# TSOC_Block_Template_Dual_PTH.net
KiCad netlist of a schematic drawn in EAGLE
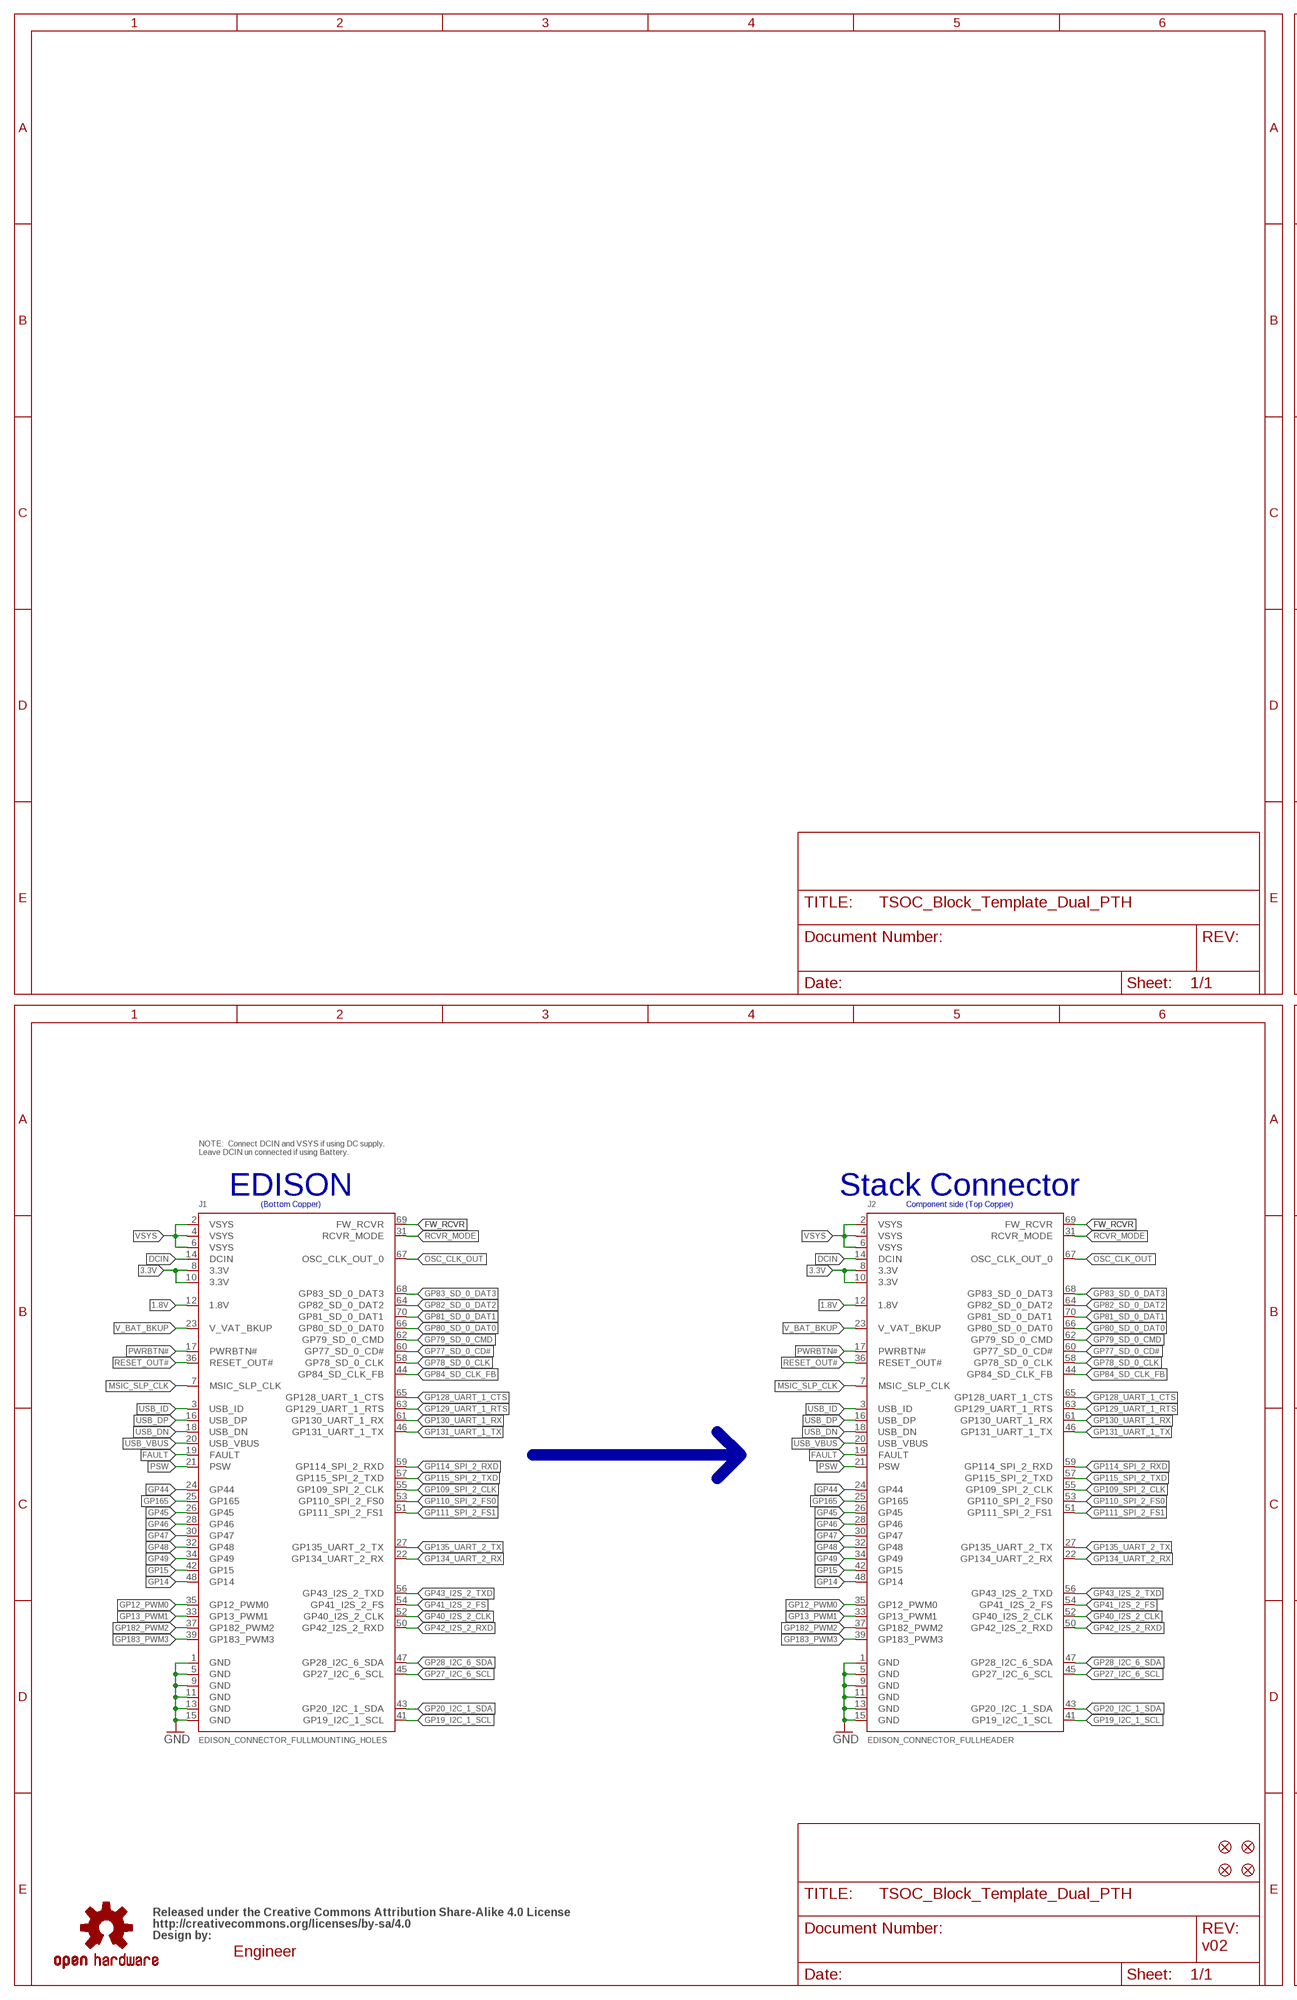
[diagram p0: schematic, sheet 1, part 1 of 2]
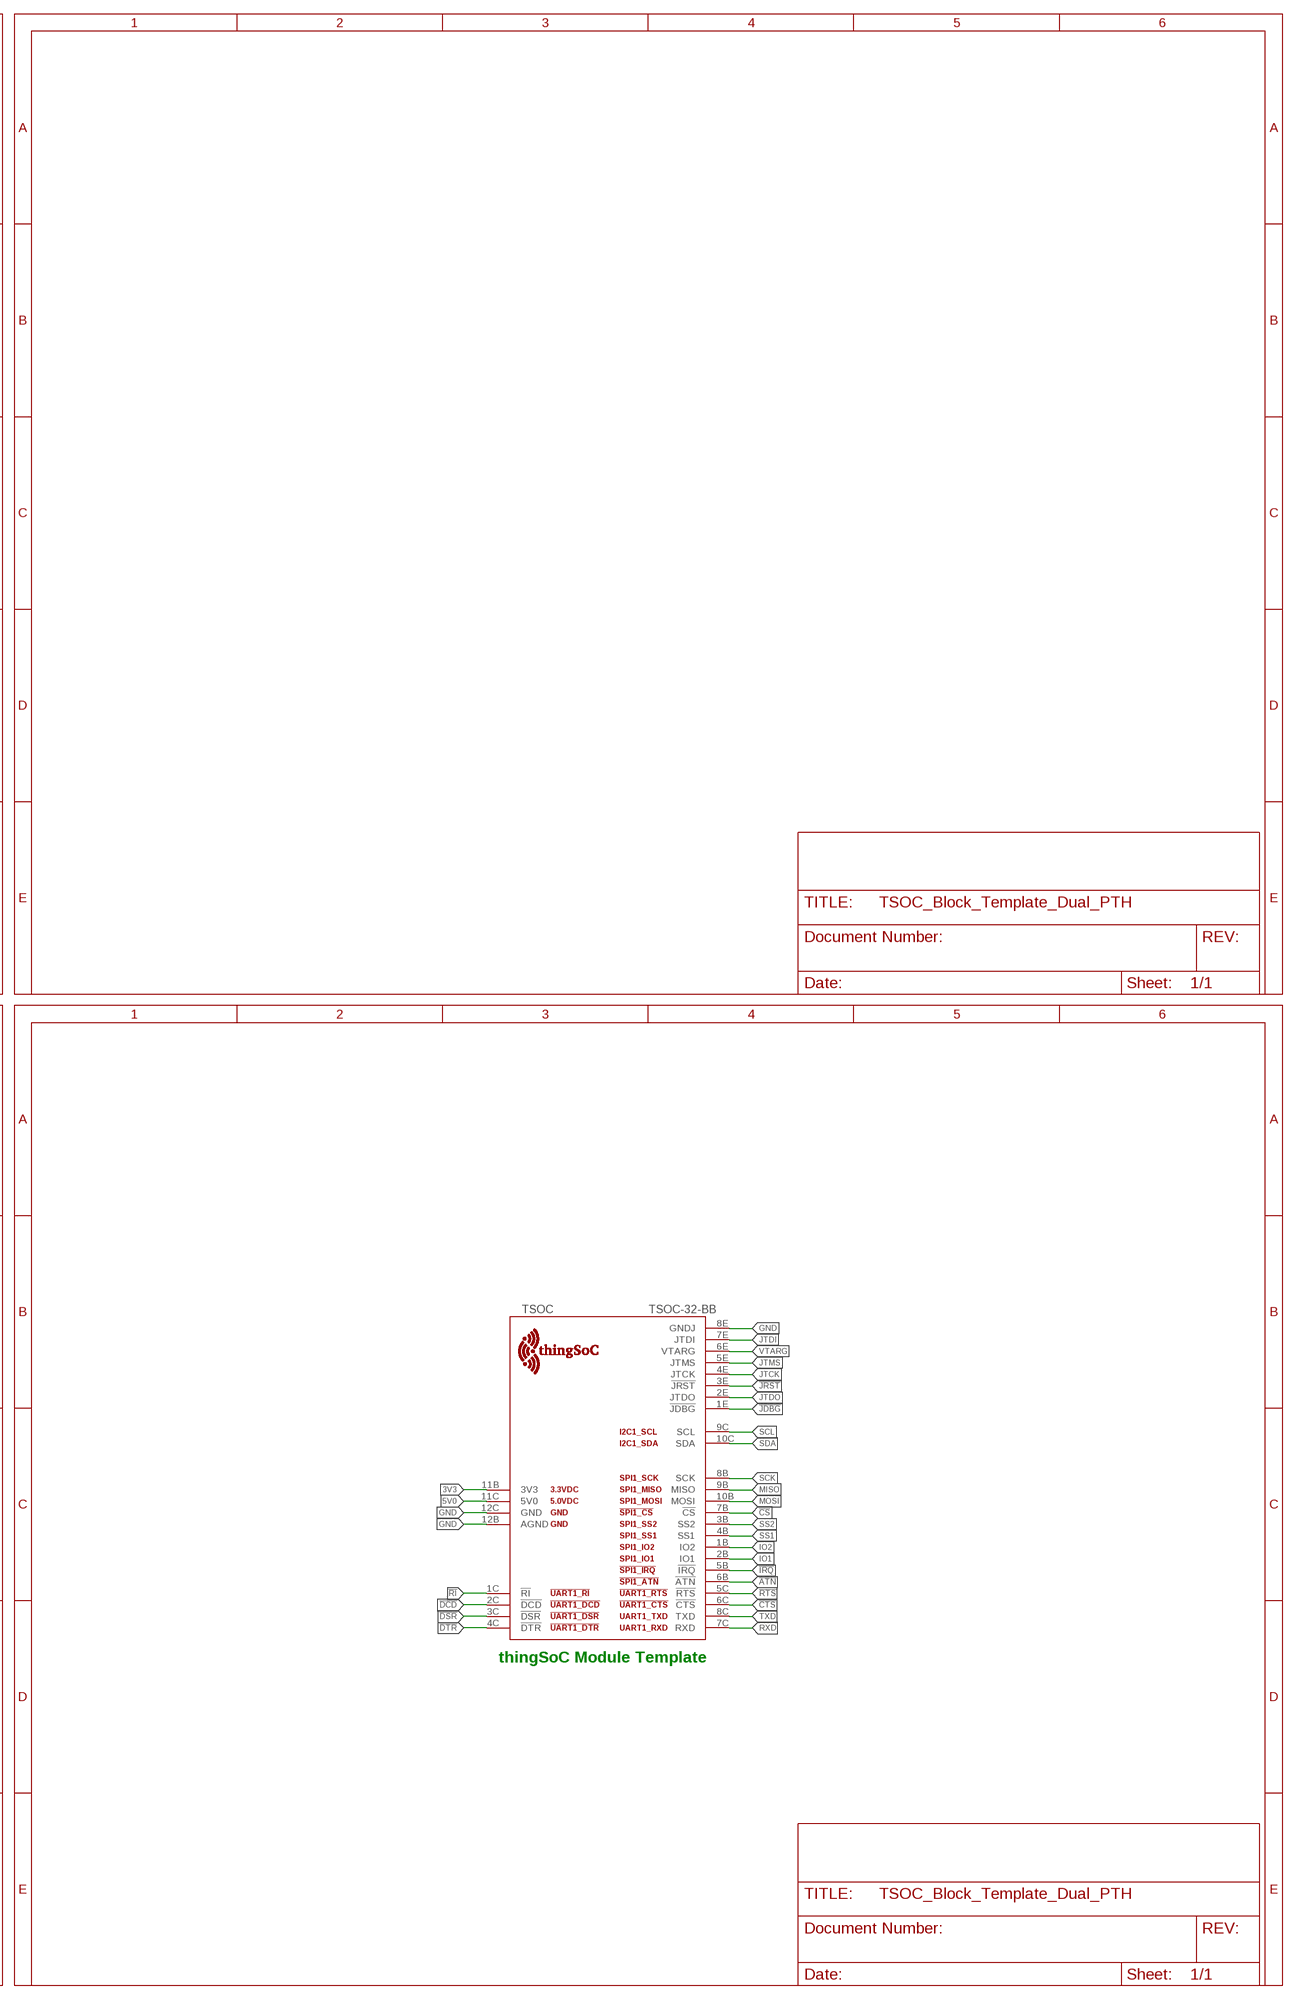
[diagram p1: schematic, sheet 1, part 2 of 2]

(export (version "E")
  (design (tool "Eeschema 10.0.6"))
  (components
    (comp (ref "FID5")
      (value "FIDUCIAL1X2")
      (footprint "eagle-import:FIDUCIAL-1X2")
      (libsource (lib "eagle-import") (part "FIDUCIAL1X2"))
    )
    (comp (ref "FID6")
      (value "FIDUCIAL1X2")
      (footprint "eagle-import:FIDUCIAL-1X2")
      (libsource (lib "eagle-import") (part "FIDUCIAL1X2"))
    )
    (comp (ref "FID7")
      (value "FIDUCIAL1X2")
      (footprint "eagle-import:FIDUCIAL-1X2")
      (libsource (lib "eagle-import") (part "FIDUCIAL1X2"))
    )
    (comp (ref "FID8")
      (value "FIDUCIAL1X2")
      (footprint "eagle-import:FIDUCIAL-1X2")
      (libsource (lib "eagle-import") (part "FIDUCIAL1X2"))
    )
    (comp (ref "J1")
      (value "EDISON_CONNECTOR_FULLMOUNTING_HOLES")
      (footprint "eagle-import:EDISON_DAUGHTER")
      (libsource (lib "eagle-import") (part "EDISON_CONNECTOR_FULLMOUNTING_HOLES"))
    )
    (comp (ref "J2")
      (value "EDISON_CONNECTOR_FULLHEADER")
      (footprint "eagle-import:DF40C-70DP-0.4(51)")
      (libsource (lib "eagle-import") (part "EDISON_CONNECTOR_FULLHEADER"))
    )
    (comp (ref "LOGO5")
      (value "OSHW-LOGOS")
      (footprint "eagle-import:OSHW-LOGO-S")
      (libsource (lib "eagle-import") (part "OSHW-LOGOS"))
    )
    (comp (ref "TSOC")
      (value "TSOC-32-BB")
      (footprint "eagle-import:TSOC-BB-S32")
      (libsource (lib "eagle-import") (part "TSOC-32-BB"))
    )
    (comp (ref "U$1")
      (value "BY_CC_SA_TEXTTEXT")
      (footprint "eagle-import:BY_CC_SA_TEXT")
      (libsource (lib "eagle-import") (part "BY_CC_SA_TEXTTEXT"))
    )
  )
  (nets
    (net (code "1") (name "/~{ATN}") (class "Default")
      (node (ref "TSOC") (pin "6B") (pinfunction "~{ATN}_6B") (pintype "bidirectional"))
    )
    (net (code "2") (name "/~{CS}") (class "Default")
      (node (ref "TSOC") (pin "7B") (pinfunction "~{CS}_7B") (pintype "bidirectional"))
    )
    (net (code "3") (name "/~{CTS}") (class "Default")
      (node (ref "TSOC") (pin "6C") (pinfunction "~{CTS}_6C") (pintype "bidirectional"))
    )
    (net (code "4") (name "/~{DCD}") (class "Default")
      (node (ref "TSOC") (pin "2C") (pinfunction "~{DCD}_2C") (pintype "bidirectional"))
    )
    (net (code "5") (name "/~{DSR}") (class "Default")
      (node (ref "TSOC") (pin "3C") (pinfunction "~{DSR}_3C") (pintype "bidirectional"))
    )
    (net (code "6") (name "/~{DTR}") (class "Default")
      (node (ref "TSOC") (pin "4C") (pinfunction "~{DTR}_4C") (pintype "bidirectional"))
    )
    (net (code "7") (name "/~{IRQ}") (class "Default")
      (node (ref "TSOC") (pin "5B") (pinfunction "~{IRQ}_5B") (pintype "bidirectional"))
    )
    (net (code "8") (name "/~{JDBG}") (class "Default")
      (node (ref "TSOC") (pin "1E") (pinfunction "~{JDBG}_1E") (pintype "bidirectional"))
    )
    (net (code "9") (name "/~{JRST}") (class "Default")
      (node (ref "TSOC") (pin "3E") (pinfunction "~{JRST}_3E") (pintype "bidirectional"))
    )
    (net (code "10") (name "/~{RI}") (class "Default")
      (node (ref "TSOC") (pin "1C") (pinfunction "~{RI}_1C") (pintype "bidirectional"))
    )
    (net (code "11") (name "/~{RTS}") (class "Default")
      (node (ref "TSOC") (pin "5C") (pinfunction "~{RTS}_5C") (pintype "bidirectional"))
    )
    (net (code "12") (name "1.8V") (class "Default")
      (node (ref "J1") (pin "12") (pinfunction "1.8V_12") (pintype "bidirectional"))
      (node (ref "J2") (pin "12") (pinfunction "1.8V_12") (pintype "bidirectional"))
    )
    (net (code "13") (name "3.3V") (class "Default")
      (node (ref "J1") (pin "10") (pinfunction "3.3V_10") (pintype "bidirectional"))
      (node (ref "J1") (pin "8") (pinfunction "3.3V_8") (pintype "bidirectional"))
      (node (ref "J2") (pin "10") (pinfunction "3.3V_10") (pintype "bidirectional"))
      (node (ref "J2") (pin "8") (pinfunction "3.3V_8") (pintype "bidirectional"))
    )
    (net (code "14") (name "3V3") (class "Default")
      (node (ref "TSOC") (pin "11B") (pinfunction "3V3_11B") (pintype "bidirectional"))
    )
    (net (code "15") (name "5V0") (class "Default")
      (node (ref "TSOC") (pin "11C") (pinfunction "5V0_11C") (pintype "bidirectional"))
    )
    (net (code "16") (name "DCIN") (class "Default")
      (node (ref "J1") (pin "14") (pinfunction "DCIN_14") (pintype "bidirectional"))
      (node (ref "J2") (pin "14") (pinfunction "DCIN_14") (pintype "bidirectional"))
    )
    (net (code "17") (name "FAULT") (class "Default")
      (node (ref "J1") (pin "19") (pinfunction "FAULT_19") (pintype "bidirectional"))
      (node (ref "J2") (pin "19") (pinfunction "FAULT_19") (pintype "bidirectional"))
    )
    (net (code "18") (name "FW_RCVR") (class "Default")
      (node (ref "J1") (pin "69") (pinfunction "FW_RCVR_69") (pintype "bidirectional"))
      (node (ref "J2") (pin "69") (pinfunction "FW_RCVR_69") (pintype "bidirectional"))
    )
    (net (code "19") (name "GND") (class "Default")
      (node (ref "J1") (pin "1") (pinfunction "GND_1") (pintype "bidirectional"))
      (node (ref "J1") (pin "11") (pinfunction "GND_11") (pintype "bidirectional"))
      (node (ref "J1") (pin "13") (pinfunction "GND_13") (pintype "bidirectional"))
      (node (ref "J1") (pin "15") (pinfunction "GND_15") (pintype "bidirectional"))
      (node (ref "J1") (pin "5") (pinfunction "GND_5") (pintype "bidirectional"))
      (node (ref "J1") (pin "9") (pinfunction "GND_9") (pintype "bidirectional"))
      (node (ref "J2") (pin "1") (pinfunction "GND_1") (pintype "bidirectional"))
      (node (ref "J2") (pin "11") (pinfunction "GND_11") (pintype "bidirectional"))
      (node (ref "J2") (pin "13") (pinfunction "GND_13") (pintype "bidirectional"))
      (node (ref "J2") (pin "15") (pinfunction "GND_15") (pintype "bidirectional"))
      (node (ref "J2") (pin "5") (pinfunction "GND_5") (pintype "bidirectional"))
      (node (ref "J2") (pin "9") (pinfunction "GND_9") (pintype "bidirectional"))
      (node (ref "TSOC") (pin "12B") (pinfunction "AGND_12B") (pintype "bidirectional"))
      (node (ref "TSOC") (pin "12C") (pinfunction "GND_12C") (pintype "bidirectional"))
      (node (ref "TSOC") (pin "8E") (pinfunction "GNDJ_8E") (pintype "bidirectional"))
    )
    (net (code "20") (name "GP12_PWM0") (class "Default")
      (node (ref "J1") (pin "35") (pinfunction "GP12_PWM0_35") (pintype "bidirectional"))
      (node (ref "J2") (pin "35") (pinfunction "GP12_PWM0_35") (pintype "bidirectional"))
    )
    (net (code "21") (name "GP13_PWM1") (class "Default")
      (node (ref "J1") (pin "33") (pinfunction "GP13_PWM1_33") (pintype "bidirectional"))
      (node (ref "J2") (pin "33") (pinfunction "GP13_PWM1_33") (pintype "bidirectional"))
    )
    (net (code "22") (name "GP14") (class "Default")
      (node (ref "J1") (pin "48") (pinfunction "GP14_48") (pintype "bidirectional"))
      (node (ref "J2") (pin "48") (pinfunction "GP14_48") (pintype "bidirectional"))
    )
    (net (code "23") (name "GP15") (class "Default")
      (node (ref "J1") (pin "42") (pinfunction "GP15_42") (pintype "bidirectional"))
      (node (ref "J2") (pin "42") (pinfunction "GP15_42") (pintype "bidirectional"))
    )
    (net (code "24") (name "GP19_I2C_1_SCL") (class "Default")
      (node (ref "J1") (pin "41") (pinfunction "GP19_I2C_1_SCL_41") (pintype "bidirectional"))
      (node (ref "J2") (pin "41") (pinfunction "GP19_I2C_1_SCL_41") (pintype "bidirectional"))
    )
    (net (code "25") (name "GP20_I2C_1_SDA") (class "Default")
      (node (ref "J1") (pin "43") (pinfunction "GP20_I2C_1_SDA_43") (pintype "bidirectional"))
      (node (ref "J2") (pin "43") (pinfunction "GP20_I2C_1_SDA_43") (pintype "bidirectional"))
    )
    (net (code "26") (name "GP27_I2C_6_SCL") (class "Default")
      (node (ref "J1") (pin "45") (pinfunction "GP27_I2C_6_SCL_45") (pintype "bidirectional"))
      (node (ref "J2") (pin "45") (pinfunction "GP27_I2C_6_SCL_45") (pintype "bidirectional"))
    )
    (net (code "27") (name "GP28_I2C_6_SDA") (class "Default")
      (node (ref "J1") (pin "47") (pinfunction "GP28_I2C_6_SDA_47") (pintype "bidirectional"))
      (node (ref "J2") (pin "47") (pinfunction "GP28_I2C_6_SDA_47") (pintype "bidirectional"))
    )
    (net (code "28") (name "GP40_I2S_2_CLK") (class "Default")
      (node (ref "J1") (pin "52") (pinfunction "GP40_I2S_2_CLK_52") (pintype "bidirectional"))
      (node (ref "J2") (pin "52") (pinfunction "GP40_I2S_2_CLK_52") (pintype "bidirectional"))
    )
    (net (code "29") (name "GP41_I2S_2_FS") (class "Default")
      (node (ref "J1") (pin "54") (pinfunction "GP41_I2S_2_FS_54") (pintype "bidirectional"))
      (node (ref "J2") (pin "54") (pinfunction "GP41_I2S_2_FS_54") (pintype "bidirectional"))
    )
    (net (code "30") (name "GP42_I2S_2_RXD") (class "Default")
      (node (ref "J1") (pin "50") (pinfunction "GP42_I2S_2_RXD_50") (pintype "bidirectional"))
      (node (ref "J2") (pin "50") (pinfunction "GP42_I2S_2_RXD_50") (pintype "bidirectional"))
    )
    (net (code "31") (name "GP43_I2S_2_TXD") (class "Default")
      (node (ref "J1") (pin "56") (pinfunction "GP43_I2S_2_TXD_56") (pintype "bidirectional"))
      (node (ref "J2") (pin "56") (pinfunction "GP43_I2S_2_TXD_56") (pintype "bidirectional"))
    )
    (net (code "32") (name "GP44") (class "Default")
      (node (ref "J1") (pin "24") (pinfunction "GP44_24") (pintype "bidirectional"))
      (node (ref "J2") (pin "24") (pinfunction "GP44_24") (pintype "bidirectional"))
    )
    (net (code "33") (name "GP45") (class "Default")
      (node (ref "J1") (pin "26") (pinfunction "GP45_26") (pintype "bidirectional"))
      (node (ref "J2") (pin "26") (pinfunction "GP45_26") (pintype "bidirectional"))
    )
    (net (code "34") (name "GP46") (class "Default")
      (node (ref "J1") (pin "28") (pinfunction "GP46_28") (pintype "bidirectional"))
      (node (ref "J2") (pin "28") (pinfunction "GP46_28") (pintype "bidirectional"))
    )
    (net (code "35") (name "GP47") (class "Default")
      (node (ref "J1") (pin "30") (pinfunction "GP47_30") (pintype "bidirectional"))
      (node (ref "J2") (pin "30") (pinfunction "GP47_30") (pintype "bidirectional"))
    )
    (net (code "36") (name "GP48") (class "Default")
      (node (ref "J1") (pin "32") (pinfunction "GP48_32") (pintype "bidirectional"))
      (node (ref "J2") (pin "32") (pinfunction "GP48_32") (pintype "bidirectional"))
    )
    (net (code "37") (name "GP49") (class "Default")
      (node (ref "J1") (pin "34") (pinfunction "GP49_34") (pintype "bidirectional"))
      (node (ref "J2") (pin "34") (pinfunction "GP49_34") (pintype "bidirectional"))
    )
    (net (code "38") (name "GP77_SD_0_CD#") (class "Default")
      (node (ref "J1") (pin "60") (pinfunction "GP77_SD_0_CD#_60") (pintype "bidirectional"))
      (node (ref "J2") (pin "60") (pinfunction "GP77_SD_0_CD#_60") (pintype "bidirectional"))
    )
    (net (code "39") (name "GP78_SD_0_CLK") (class "Default")
      (node (ref "J1") (pin "58") (pinfunction "GP78_SD_0_CLK_58") (pintype "bidirectional"))
      (node (ref "J2") (pin "58") (pinfunction "GP78_SD_0_CLK_58") (pintype "bidirectional"))
    )
    (net (code "40") (name "GP79_SD_0_CMD") (class "Default")
      (node (ref "J1") (pin "62") (pinfunction "GP79_SD_0_CMD_62") (pintype "bidirectional"))
      (node (ref "J2") (pin "62") (pinfunction "GP79_SD_0_CMD_62") (pintype "bidirectional"))
    )
    (net (code "41") (name "GP80_SD_0_DAT0") (class "Default")
      (node (ref "J1") (pin "66") (pinfunction "GP80_SD_0_DAT0_66") (pintype "bidirectional"))
      (node (ref "J2") (pin "66") (pinfunction "GP80_SD_0_DAT0_66") (pintype "bidirectional"))
    )
    (net (code "42") (name "GP81_SD_0_DAT1") (class "Default")
      (node (ref "J1") (pin "70") (pinfunction "GP81_SD_0_DAT1_70") (pintype "bidirectional"))
      (node (ref "J2") (pin "70") (pinfunction "GP81_SD_0_DAT1_70") (pintype "bidirectional"))
    )
    (net (code "43") (name "GP82_SD_0_DAT2") (class "Default")
      (node (ref "J1") (pin "64") (pinfunction "GP82_SD_0_DAT2_64") (pintype "bidirectional"))
      (node (ref "J2") (pin "64") (pinfunction "GP82_SD_0_DAT2_64") (pintype "bidirectional"))
    )
    (net (code "44") (name "GP83_SD_0_DAT3") (class "Default")
      (node (ref "J1") (pin "68") (pinfunction "GP83_SD_0_DAT3_68") (pintype "bidirectional"))
      (node (ref "J2") (pin "68") (pinfunction "GP83_SD_0_DAT3_68") (pintype "bidirectional"))
    )
    (net (code "45") (name "GP84_SD_CLK_FB") (class "Default")
      (node (ref "J1") (pin "44") (pinfunction "GP84_SD_CLK_FB_44") (pintype "bidirectional"))
      (node (ref "J2") (pin "44") (pinfunction "GP84_SD_CLK_FB_44") (pintype "bidirectional"))
    )
    (net (code "46") (name "GP109_SPI_2_CLK") (class "Default")
      (node (ref "J1") (pin "55") (pinfunction "GP109_SPI_2_CLK_55") (pintype "bidirectional"))
      (node (ref "J2") (pin "55") (pinfunction "GP109_SPI_2_CLK_55") (pintype "bidirectional"))
    )
    (net (code "47") (name "GP110_SPI_2_FS0") (class "Default")
      (node (ref "J1") (pin "53") (pinfunction "GP110_SPI_2_FS0_53") (pintype "bidirectional"))
      (node (ref "J2") (pin "53") (pinfunction "GP110_SPI_2_FS0_53") (pintype "bidirectional"))
    )
    (net (code "48") (name "GP111_SPI_2_FS1") (class "Default")
      (node (ref "J1") (pin "51") (pinfunction "GP111_SPI_2_FS1_51") (pintype "bidirectional"))
      (node (ref "J2") (pin "51") (pinfunction "GP111_SPI_2_FS1_51") (pintype "bidirectional"))
    )
    (net (code "49") (name "GP114_SPI_2_RXD") (class "Default")
      (node (ref "J1") (pin "59") (pinfunction "GP114_SPI_2_RXD_59") (pintype "bidirectional"))
      (node (ref "J2") (pin "59") (pinfunction "GP114_SPI_2_RXD_59") (pintype "bidirectional"))
    )
    (net (code "50") (name "GP115_SPI_2_TXD") (class "Default")
      (node (ref "J1") (pin "57") (pinfunction "GP115_SPI_2_TXD_57") (pintype "bidirectional"))
      (node (ref "J2") (pin "57") (pinfunction "GP115_SPI_2_TXD_57") (pintype "bidirectional"))
    )
    (net (code "51") (name "GP128_UART_1_CTS") (class "Default")
      (node (ref "J1") (pin "65") (pinfunction "GP128_UART_1_CTS_65") (pintype "bidirectional"))
      (node (ref "J2") (pin "65") (pinfunction "GP128_UART_1_CTS_65") (pintype "bidirectional"))
    )
    (net (code "52") (name "GP129_UART_1_RTS") (class "Default")
      (node (ref "J1") (pin "63") (pinfunction "GP129_UART_1_RTS_63") (pintype "bidirectional"))
      (node (ref "J2") (pin "63") (pinfunction "GP129_UART_1_RTS_63") (pintype "bidirectional"))
    )
    (net (code "53") (name "GP130_UART_1_RX") (class "Default")
      (node (ref "J1") (pin "61") (pinfunction "GP130_UART_1_RX_61") (pintype "bidirectional"))
      (node (ref "J2") (pin "61") (pinfunction "GP130_UART_1_RX_61") (pintype "bidirectional"))
    )
    (net (code "54") (name "GP131_UART_1_TX") (class "Default")
      (node (ref "J1") (pin "46") (pinfunction "GP131_UART_1_TX_46") (pintype "bidirectional"))
      (node (ref "J2") (pin "46") (pinfunction "GP131_UART_1_TX_46") (pintype "bidirectional"))
    )
    (net (code "55") (name "GP134_UART_2_RX") (class "Default")
      (node (ref "J1") (pin "22") (pinfunction "GP134_UART_2_RX_22") (pintype "bidirectional"))
      (node (ref "J2") (pin "22") (pinfunction "GP134_UART_2_RX_22") (pintype "bidirectional"))
    )
    (net (code "56") (name "GP135_UART_2_TX") (class "Default")
      (node (ref "J1") (pin "27") (pinfunction "GP135_UART_2_TX_27") (pintype "bidirectional"))
      (node (ref "J2") (pin "27") (pinfunction "GP135_UART_2_TX_27") (pintype "bidirectional"))
    )
    (net (code "57") (name "GP165") (class "Default")
      (node (ref "J1") (pin "25") (pinfunction "GP165_25") (pintype "bidirectional"))
      (node (ref "J2") (pin "25") (pinfunction "GP165_25") (pintype "bidirectional"))
    )
    (net (code "58") (name "GP182_PWM2") (class "Default")
      (node (ref "J1") (pin "37") (pinfunction "GP182_PWM2_37") (pintype "bidirectional"))
      (node (ref "J2") (pin "37") (pinfunction "GP182_PWM2_37") (pintype "bidirectional"))
    )
    (net (code "59") (name "GP183_PWM3") (class "Default")
      (node (ref "J1") (pin "39") (pinfunction "GP183_PWM3_39") (pintype "bidirectional"))
      (node (ref "J2") (pin "39") (pinfunction "GP183_PWM3_39") (pintype "bidirectional"))
    )
    (net (code "60") (name "IO1") (class "Default")
      (node (ref "TSOC") (pin "2B") (pinfunction "IO1_2B") (pintype "bidirectional"))
    )
    (net (code "61") (name "IO2") (class "Default")
      (node (ref "TSOC") (pin "1B") (pinfunction "IO2_1B") (pintype "bidirectional"))
    )
    (net (code "62") (name "JTCK") (class "Default")
      (node (ref "TSOC") (pin "4E") (pinfunction "JTCK_4E") (pintype "bidirectional"))
    )
    (net (code "63") (name "JTDI") (class "Default")
      (node (ref "TSOC") (pin "7E") (pinfunction "JTDI_7E") (pintype "bidirectional"))
    )
    (net (code "64") (name "JTDO") (class "Default")
      (node (ref "TSOC") (pin "2E") (pinfunction "JTDO_2E") (pintype "bidirectional"))
    )
    (net (code "65") (name "JTMS") (class "Default")
      (node (ref "TSOC") (pin "5E") (pinfunction "JTMS_5E") (pintype "bidirectional"))
    )
    (net (code "66") (name "MISO") (class "Default")
      (node (ref "TSOC") (pin "9B") (pinfunction "MISO_9B") (pintype "bidirectional"))
    )
    (net (code "67") (name "MOSI") (class "Default")
      (node (ref "TSOC") (pin "10B") (pinfunction "MOSI_10B") (pintype "bidirectional"))
    )
    (net (code "68") (name "MSIC_SLP_CLK") (class "Default")
      (node (ref "J1") (pin "7") (pinfunction "MSIC_SLP_CLK_7") (pintype "bidirectional"))
      (node (ref "J2") (pin "7") (pinfunction "MSIC_SLP_CLK_7") (pintype "bidirectional"))
    )
    (net (code "69") (name "OSC_CLK_OUT") (class "Default")
      (node (ref "J1") (pin "67") (pinfunction "OSC_CLK_OUT_0_67") (pintype "bidirectional"))
      (node (ref "J2") (pin "67") (pinfunction "OSC_CLK_OUT_0_67") (pintype "bidirectional"))
    )
    (net (code "70") (name "PSW") (class "Default")
      (node (ref "J1") (pin "21") (pinfunction "PSW_21") (pintype "bidirectional"))
      (node (ref "J2") (pin "21") (pinfunction "PSW_21") (pintype "bidirectional"))
    )
    (net (code "71") (name "PWRBTN#") (class "Default")
      (node (ref "J1") (pin "17") (pinfunction "PWRBTN#_17") (pintype "bidirectional"))
      (node (ref "J2") (pin "17") (pinfunction "PWRBTN#_17") (pintype "bidirectional"))
    )
    (net (code "72") (name "RCVR_MODE") (class "Default")
      (node (ref "J1") (pin "31") (pinfunction "RCVR_MODE_31") (pintype "bidirectional"))
      (node (ref "J2") (pin "31") (pinfunction "RCVR_MODE_31") (pintype "bidirectional"))
    )
    (net (code "73") (name "RESET_OUT#") (class "Default")
      (node (ref "J1") (pin "36") (pinfunction "RESET_OUT#_36") (pintype "bidirectional"))
      (node (ref "J2") (pin "36") (pinfunction "RESET_OUT#_36") (pintype "bidirectional"))
    )
    (net (code "74") (name "RXD") (class "Default")
      (node (ref "TSOC") (pin "7C") (pinfunction "RXD_7C") (pintype "bidirectional"))
    )
    (net (code "75") (name "SCK") (class "Default")
      (node (ref "TSOC") (pin "8B") (pinfunction "SCK_8B") (pintype "bidirectional"))
    )
    (net (code "76") (name "SCL") (class "Default")
      (node (ref "TSOC") (pin "9C") (pinfunction "SCL_9C") (pintype "bidirectional"))
    )
    (net (code "77") (name "SDA") (class "Default")
      (node (ref "TSOC") (pin "10C") (pinfunction "SDA_10C") (pintype "bidirectional"))
    )
    (net (code "78") (name "SS1") (class "Default")
      (node (ref "TSOC") (pin "4B") (pinfunction "SS1_4B") (pintype "bidirectional"))
    )
    (net (code "79") (name "SS2") (class "Default")
      (node (ref "TSOC") (pin "3B") (pinfunction "SS2_3B") (pintype "bidirectional"))
    )
    (net (code "80") (name "TXD") (class "Default")
      (node (ref "TSOC") (pin "8C") (pinfunction "TXD_8C") (pintype "bidirectional"))
    )
    (net (code "81") (name "USB_DN") (class "Default")
      (node (ref "J1") (pin "18") (pinfunction "USB_DN_18") (pintype "bidirectional"))
      (node (ref "J2") (pin "18") (pinfunction "USB_DN_18") (pintype "bidirectional"))
    )
    (net (code "82") (name "USB_DP") (class "Default")
      (node (ref "J1") (pin "16") (pinfunction "USB_DP_16") (pintype "bidirectional"))
      (node (ref "J2") (pin "16") (pinfunction "USB_DP_16") (pintype "bidirectional"))
    )
    (net (code "83") (name "USB_ID") (class "Default")
      (node (ref "J1") (pin "3") (pinfunction "USB_ID_3") (pintype "bidirectional"))
      (node (ref "J2") (pin "3") (pinfunction "USB_ID_3") (pintype "bidirectional"))
    )
    (net (code "84") (name "USB_VBUS") (class "Default")
      (node (ref "J1") (pin "20") (pinfunction "USB_VBUS_20") (pintype "bidirectional"))
      (node (ref "J2") (pin "20") (pinfunction "USB_VBUS_20") (pintype "bidirectional"))
    )
    (net (code "85") (name "VSYS") (class "Default")
      (node (ref "J1") (pin "2") (pinfunction "VSYS_2") (pintype "bidirectional"))
      (node (ref "J1") (pin "4") (pinfunction "VSYS_4") (pintype "bidirectional"))
      (node (ref "J1") (pin "6") (pinfunction "VSYS_6") (pintype "bidirectional"))
      (node (ref "J2") (pin "2") (pinfunction "VSYS_2") (pintype "bidirectional"))
      (node (ref "J2") (pin "4") (pinfunction "VSYS_4") (pintype "bidirectional"))
      (node (ref "J2") (pin "6") (pinfunction "VSYS_6") (pintype "bidirectional"))
    )
    (net (code "86") (name "VTARG") (class "Default")
      (node (ref "TSOC") (pin "6E") (pinfunction "VTARG_6E") (pintype "bidirectional"))
    )
    (net (code "87") (name "V_BAT_BKUP") (class "Default")
      (node (ref "J1") (pin "23") (pinfunction "V_VAT_BKUP_23") (pintype "bidirectional"))
      (node (ref "J2") (pin "23") (pinfunction "V_VAT_BKUP_23") (pintype "bidirectional"))
    )
  )
)
